# schematic_file_source.net
KiCad netlist of a schematic drawn in EasyEDA
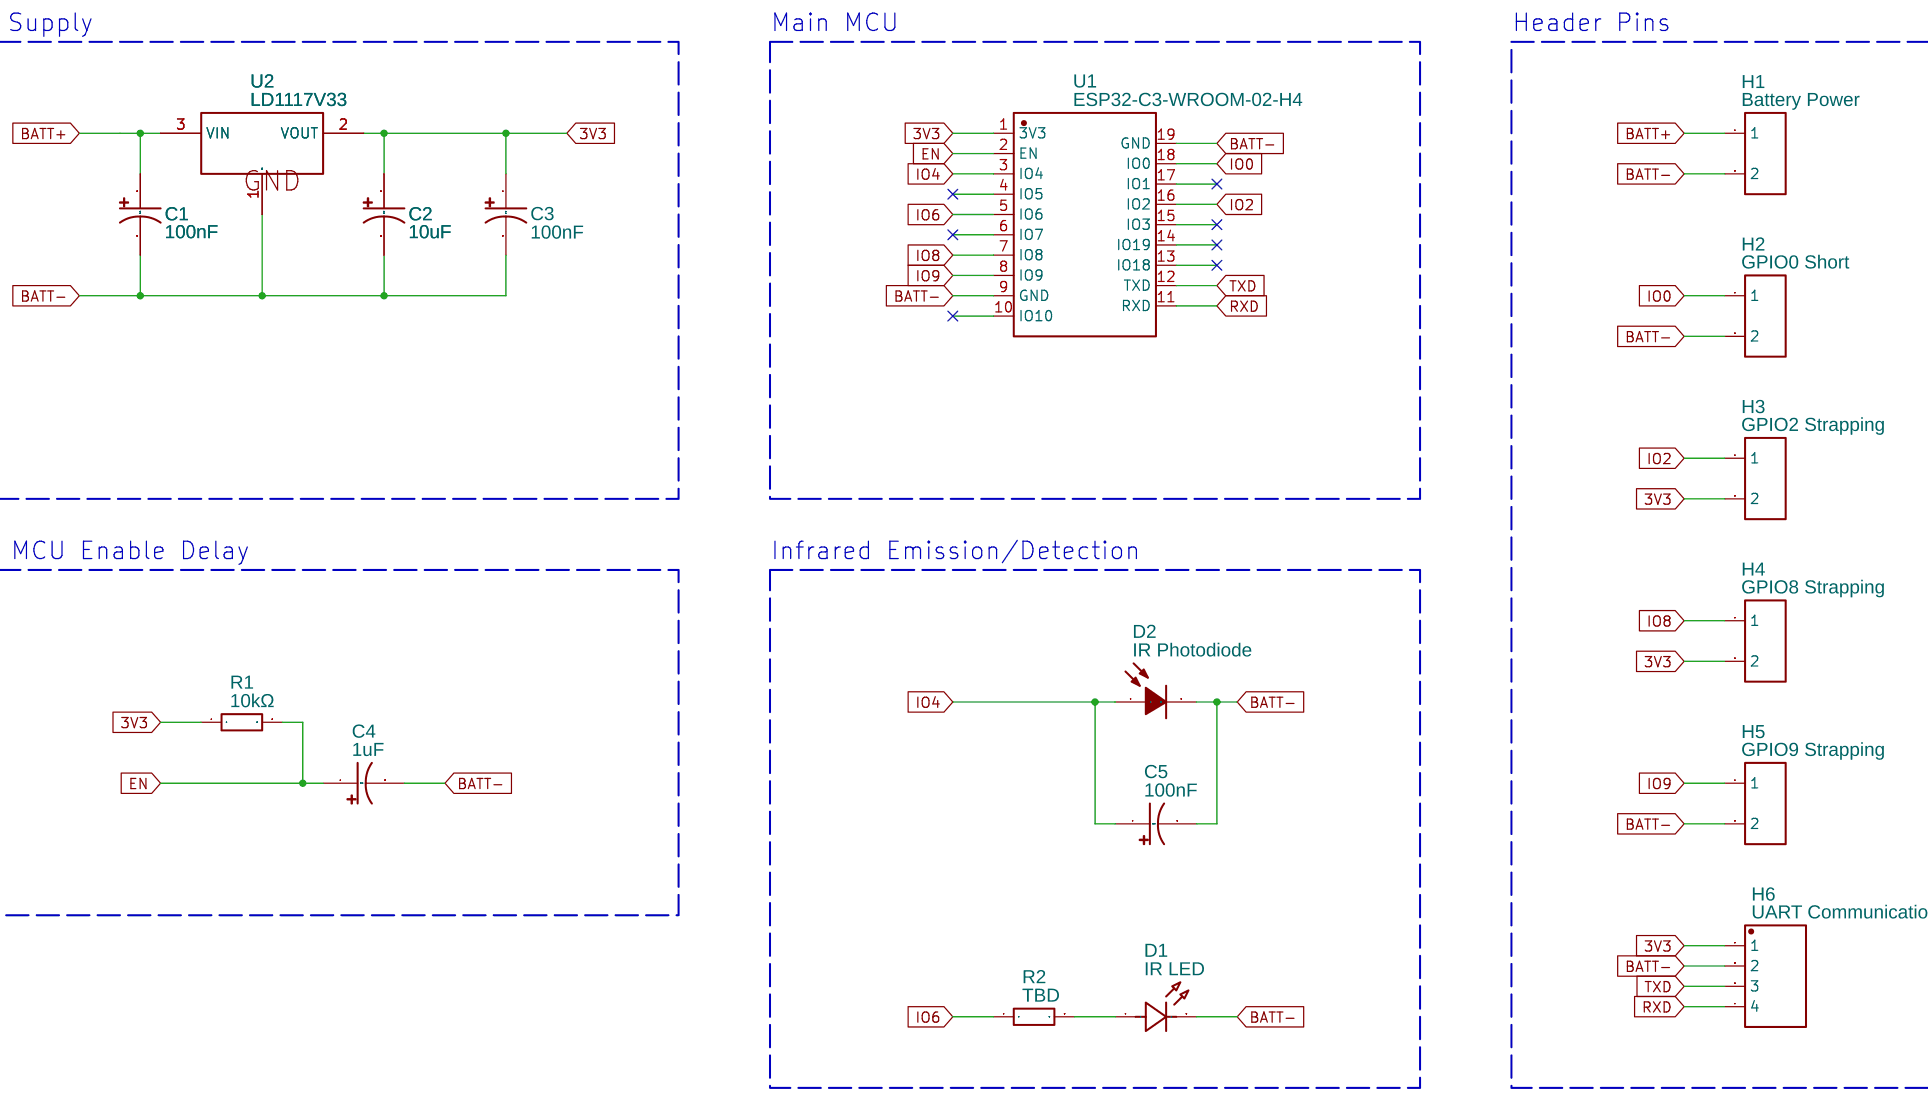
[diagram p0: schematic sheet]

(export (version "E")
  (design (tool "Eeschema 10.0.6"))
  (components
    (comp (ref "C1")
      (value "100nF")
      (fields (field (name "Manufacturer Part") "RK1052GMD122RB") (field (name "Manufacturer") "Xunda(讯达)"))
      (libsource (lib "") (part "RK1052GMD122RB_2"))
    )
    (comp (ref "C2")
      (value "10uF")
      (fields (field (name "Manufacturer Part") "RK1052GMD122RB") (field (name "Manufacturer") "Xunda(讯达)"))
      (libsource (lib "") (part "RK1052GMD122RB"))
    )
    (comp (ref "C3")
      (value "100nF")
      (fields (field (name "Manufacturer Part") "RK1052GMD122RB") (field (name "Manufacturer") "Xunda(讯达)"))
      (libsource (lib "") (part "RK1052GMD122RB"))
    )
    (comp (ref "C4")
      (value "1uF")
      (fields (field (name "Manufacturer Part") "RK1052GMD122RB") (field (name "Manufacturer") "Xunda(讯达)"))
      (libsource (lib "") (part "RK1052GMD122RB_1"))
    )
    (comp (ref "C5")
      (value "100nF")
      (fields (field (name "Manufacturer Part") "RK1052GMD122RB") (field (name "Manufacturer") "Xunda(讯达)"))
      (libsource (lib "") (part "RK1052GMD122RB_1"))
    )
    (comp (ref "D1")
      (value "IR LED")
      (fields (field (name "Manufacturer Part") "15400594F3590") (field (name "Manufacturer") "Wurth(伍尔特)"))
      (libsource (lib "") (part "15400594F3590"))
    )
    (comp (ref "D2")
      (value "IR Photodiode")
      (fields (field (name "Manufacturer Part") "MHL590PD03BRT") (field (name "Manufacturer") "MEIHUA(美华)"))
      (libsource (lib "") (part "MHL590PD03BRT"))
    )
    (comp (ref "H1")
      (value "Battery Power")
      (fields
        (field (name "Manufacturer Part") "826629-2")
        (field (name "Manufacturer") "TE Connectivity(泰科电子)")
      )
      (libsource (lib "") (part "Header-Male-2.54_1x2"))
    )
    (comp (ref "H2")
      (value "GPIO0 Short")
      (fields
        (field (name "Manufacturer Part") "826629-2")
        (field (name "Manufacturer") "TE Connectivity(泰科电子)")
      )
      (libsource (lib "") (part "Header-Male-2.54_1x2"))
    )
    (comp (ref "H3")
      (value "GPIO2 Strapping")
      (fields
        (field (name "Manufacturer Part") "826629-2")
        (field (name "Manufacturer") "TE Connectivity(泰科电子)")
      )
      (libsource (lib "") (part "Header-Male-2.54_1x2"))
    )
    (comp (ref "H4")
      (value "GPIO8 Strapping")
      (fields
        (field (name "Manufacturer Part") "826629-2")
        (field (name "Manufacturer") "TE Connectivity(泰科电子)")
      )
      (libsource (lib "") (part "Header-Male-2.54_1x2"))
    )
    (comp (ref "H5")
      (value "GPIO9 Strapping")
      (fields
        (field (name "Manufacturer Part") "826629-2")
        (field (name "Manufacturer") "TE Connectivity(泰科电子)")
      )
      (libsource (lib "") (part "Header-Male-2.54_1x2"))
    )
    (comp (ref "H6")
      (value "UART Communication")
      (fields (field (name "Manufacturer Part") "B-2100S04P-A110") (field (name "Manufacturer") "Ckmtw(灿科盟)"))
      (libsource (lib "") (part "Header-Male-2.54_1x4"))
    )
    (comp (ref "R1")
      (value "10kΩ")
      (fields
        (field (name "Manufacturer Part") "RI40-1/4W-10KΩ ±5% T")
        (field (name "Manufacturer") "CCO(千志电子)")
      )
      (libsource (lib "") (part "RI40-1/4W-10KΩ ±5% T"))
    )
    (comp (ref "R2")
      (value "TBD")
      (fields
        (field (name "Manufacturer Part") "RI40-1/4W-10KΩ ±5% T")
        (field (name "Manufacturer") "CCO(千志电子)")
      )
      (libsource (lib "") (part "RI40-1/4W-10KΩ ±5% T"))
    )
    (comp (ref "U1")
      (value "ESP32-C3-WROOM-02-H4")
      (fields (field (name "Manufacturer") "ESPRESSIF(乐鑫)"))
      (libsource (lib "") (part "ESP32-C3-WROOM-02-H4"))
    )
    (comp (ref "U2")
      (value "LD1117V33")
      (fields (field (name "Manufacturer") "ST(意法半导体)"))
      (libsource (lib "") (part "LD1117V33"))
    )
  )
  (nets
    (net (code "1") (name "3V3") (class "Default")
      (node (ref "C2") (pin "1") (pinfunction "1_1") (pintype "unspecified"))
      (node (ref "C3") (pin "1") (pinfunction "1_1") (pintype "unspecified"))
      (node (ref "H3") (pin "2") (pinfunction "2_2") (pintype "unspecified"))
      (node (ref "H4") (pin "2") (pinfunction "2_2") (pintype "unspecified"))
      (node (ref "H6") (pin "1") (pinfunction "1_1") (pintype "unspecified"))
      (node (ref "R1") (pin "1") (pinfunction "1_1") (pintype "unspecified"))
      (node (ref "U1") (pin "1") (pinfunction "3V3_1") (pintype "unspecified"))
      (node (ref "U2") (pin "2") (pinfunction "VOUT_2") (pintype "passive"))
    )
    (net (code "2") (name "BATT+") (class "Default")
      (node (ref "C1") (pin "1") (pinfunction "1_1") (pintype "unspecified"))
      (node (ref "H1") (pin "1") (pinfunction "1_1") (pintype "unspecified"))
      (node (ref "U2") (pin "3") (pinfunction "VIN_3") (pintype "passive"))
    )
    (net (code "3") (name "BATT-") (class "Default")
      (node (ref "C1") (pin "2") (pinfunction "2_2") (pintype "unspecified"))
      (node (ref "C2") (pin "2") (pinfunction "2_2") (pintype "unspecified"))
      (node (ref "C3") (pin "2") (pinfunction "2_2") (pintype "unspecified"))
      (node (ref "C4") (pin "2") (pinfunction "2_2") (pintype "unspecified"))
      (node (ref "C5") (pin "2") (pinfunction "2_2") (pintype "unspecified"))
      (node (ref "D1") (pin "2") (pinfunction "K_2") (pintype "unspecified"))
      (node (ref "D2") (pin "2") (pinfunction "C_2") (pintype "unspecified"))
      (node (ref "H1") (pin "2") (pinfunction "2_2") (pintype "unspecified"))
      (node (ref "H2") (pin "2") (pinfunction "2_2") (pintype "unspecified"))
      (node (ref "H5") (pin "2") (pinfunction "2_2") (pintype "unspecified"))
      (node (ref "H6") (pin "2") (pinfunction "2_2") (pintype "unspecified"))
      (node (ref "U1") (pin "19") (pinfunction "GND_19") (pintype "unspecified"))
      (node (ref "U1") (pin "9") (pinfunction "GND_9") (pintype "unspecified"))
      (node (ref "U2") (pin "1") (pinfunction "GND_1") (pintype "unspecified"))
    )
    (net (code "4") (name "EN") (class "Default")
      (node (ref "C4") (pin "1") (pinfunction "1_1") (pintype "unspecified"))
      (node (ref "R1") (pin "2") (pinfunction "2_2") (pintype "unspecified"))
      (node (ref "U1") (pin "2") (pinfunction "EN_2") (pintype "unspecified"))
    )
    (net (code "5") (name "IO0") (class "Default")
      (node (ref "H2") (pin "1") (pinfunction "1_1") (pintype "unspecified"))
      (node (ref "U1") (pin "18") (pinfunction "IO0_18") (pintype "unspecified"))
    )
    (net (code "6") (name "IO2") (class "Default")
      (node (ref "H3") (pin "1") (pinfunction "1_1") (pintype "unspecified"))
      (node (ref "U1") (pin "16") (pinfunction "IO2_16") (pintype "unspecified"))
    )
    (net (code "7") (name "IO4") (class "Default")
      (node (ref "C5") (pin "1") (pinfunction "1_1") (pintype "unspecified"))
      (node (ref "D2") (pin "1") (pinfunction "A_1") (pintype "unspecified"))
      (node (ref "U1") (pin "3") (pinfunction "IO4_3") (pintype "unspecified"))
    )
    (net (code "8") (name "IO6") (class "Default")
      (node (ref "R2") (pin "1") (pinfunction "1_1") (pintype "unspecified"))
      (node (ref "U1") (pin "5") (pinfunction "IO6_5") (pintype "unspecified"))
    )
    (net (code "9") (name "IO8") (class "Default")
      (node (ref "H4") (pin "1") (pinfunction "1_1") (pintype "unspecified"))
      (node (ref "U1") (pin "7") (pinfunction "IO8_7") (pintype "unspecified"))
    )
    (net (code "10") (name "IO9") (class "Default")
      (node (ref "H5") (pin "1") (pinfunction "1_1") (pintype "unspecified"))
      (node (ref "U1") (pin "8") (pinfunction "IO9_8") (pintype "unspecified"))
    )
    (net (code "11") (name "Net-(D1-A)") (class "Default")
      (node (ref "D1") (pin "1") (pinfunction "A_1") (pintype "unspecified"))
      (node (ref "R2") (pin "2") (pinfunction "2_2") (pintype "unspecified"))
    )
    (net (code "12") (name "RXD") (class "Default")
      (node (ref "H6") (pin "4") (pinfunction "4_4") (pintype "unspecified"))
      (node (ref "U1") (pin "11") (pinfunction "RXD_11") (pintype "unspecified"))
    )
    (net (code "13") (name "TXD") (class "Default")
      (node (ref "H6") (pin "3") (pinfunction "3_3") (pintype "unspecified"))
      (node (ref "U1") (pin "12") (pinfunction "TXD_12") (pintype "unspecified"))
    )
    (net (code "14") (name "unconnected-(U1-IO1-Pad17)") (class "Default")
      (node (ref "U1") (pin "17") (pinfunction "IO1_17") (pintype "unspecified+no_connect"))
    )
    (net (code "15") (name "unconnected-(U1-IO3-Pad15)") (class "Default")
      (node (ref "U1") (pin "15") (pinfunction "IO3_15") (pintype "unspecified+no_connect"))
    )
    (net (code "16") (name "unconnected-(U1-IO5-Pad4)") (class "Default")
      (node (ref "U1") (pin "4") (pinfunction "IO5_4") (pintype "unspecified+no_connect"))
    )
    (net (code "17") (name "unconnected-(U1-IO7-Pad6)") (class "Default")
      (node (ref "U1") (pin "6") (pinfunction "IO7_6") (pintype "unspecified+no_connect"))
    )
    (net (code "18") (name "unconnected-(U1-IO10-Pad10)") (class "Default")
      (node (ref "U1") (pin "10") (pinfunction "IO10_10") (pintype "unspecified+no_connect"))
    )
    (net (code "19") (name "unconnected-(U1-IO18-Pad13)") (class "Default")
      (node (ref "U1") (pin "13") (pinfunction "IO18_13") (pintype "unspecified+no_connect"))
    )
    (net (code "20") (name "unconnected-(U1-IO19-Pad14)") (class "Default")
      (node (ref "U1") (pin "14") (pinfunction "IO19_14") (pintype "unspecified+no_connect"))
    )
  )
)
